# 14_Clocks_1.net
KiCad netlist of a schematic drawn in Altium Designer
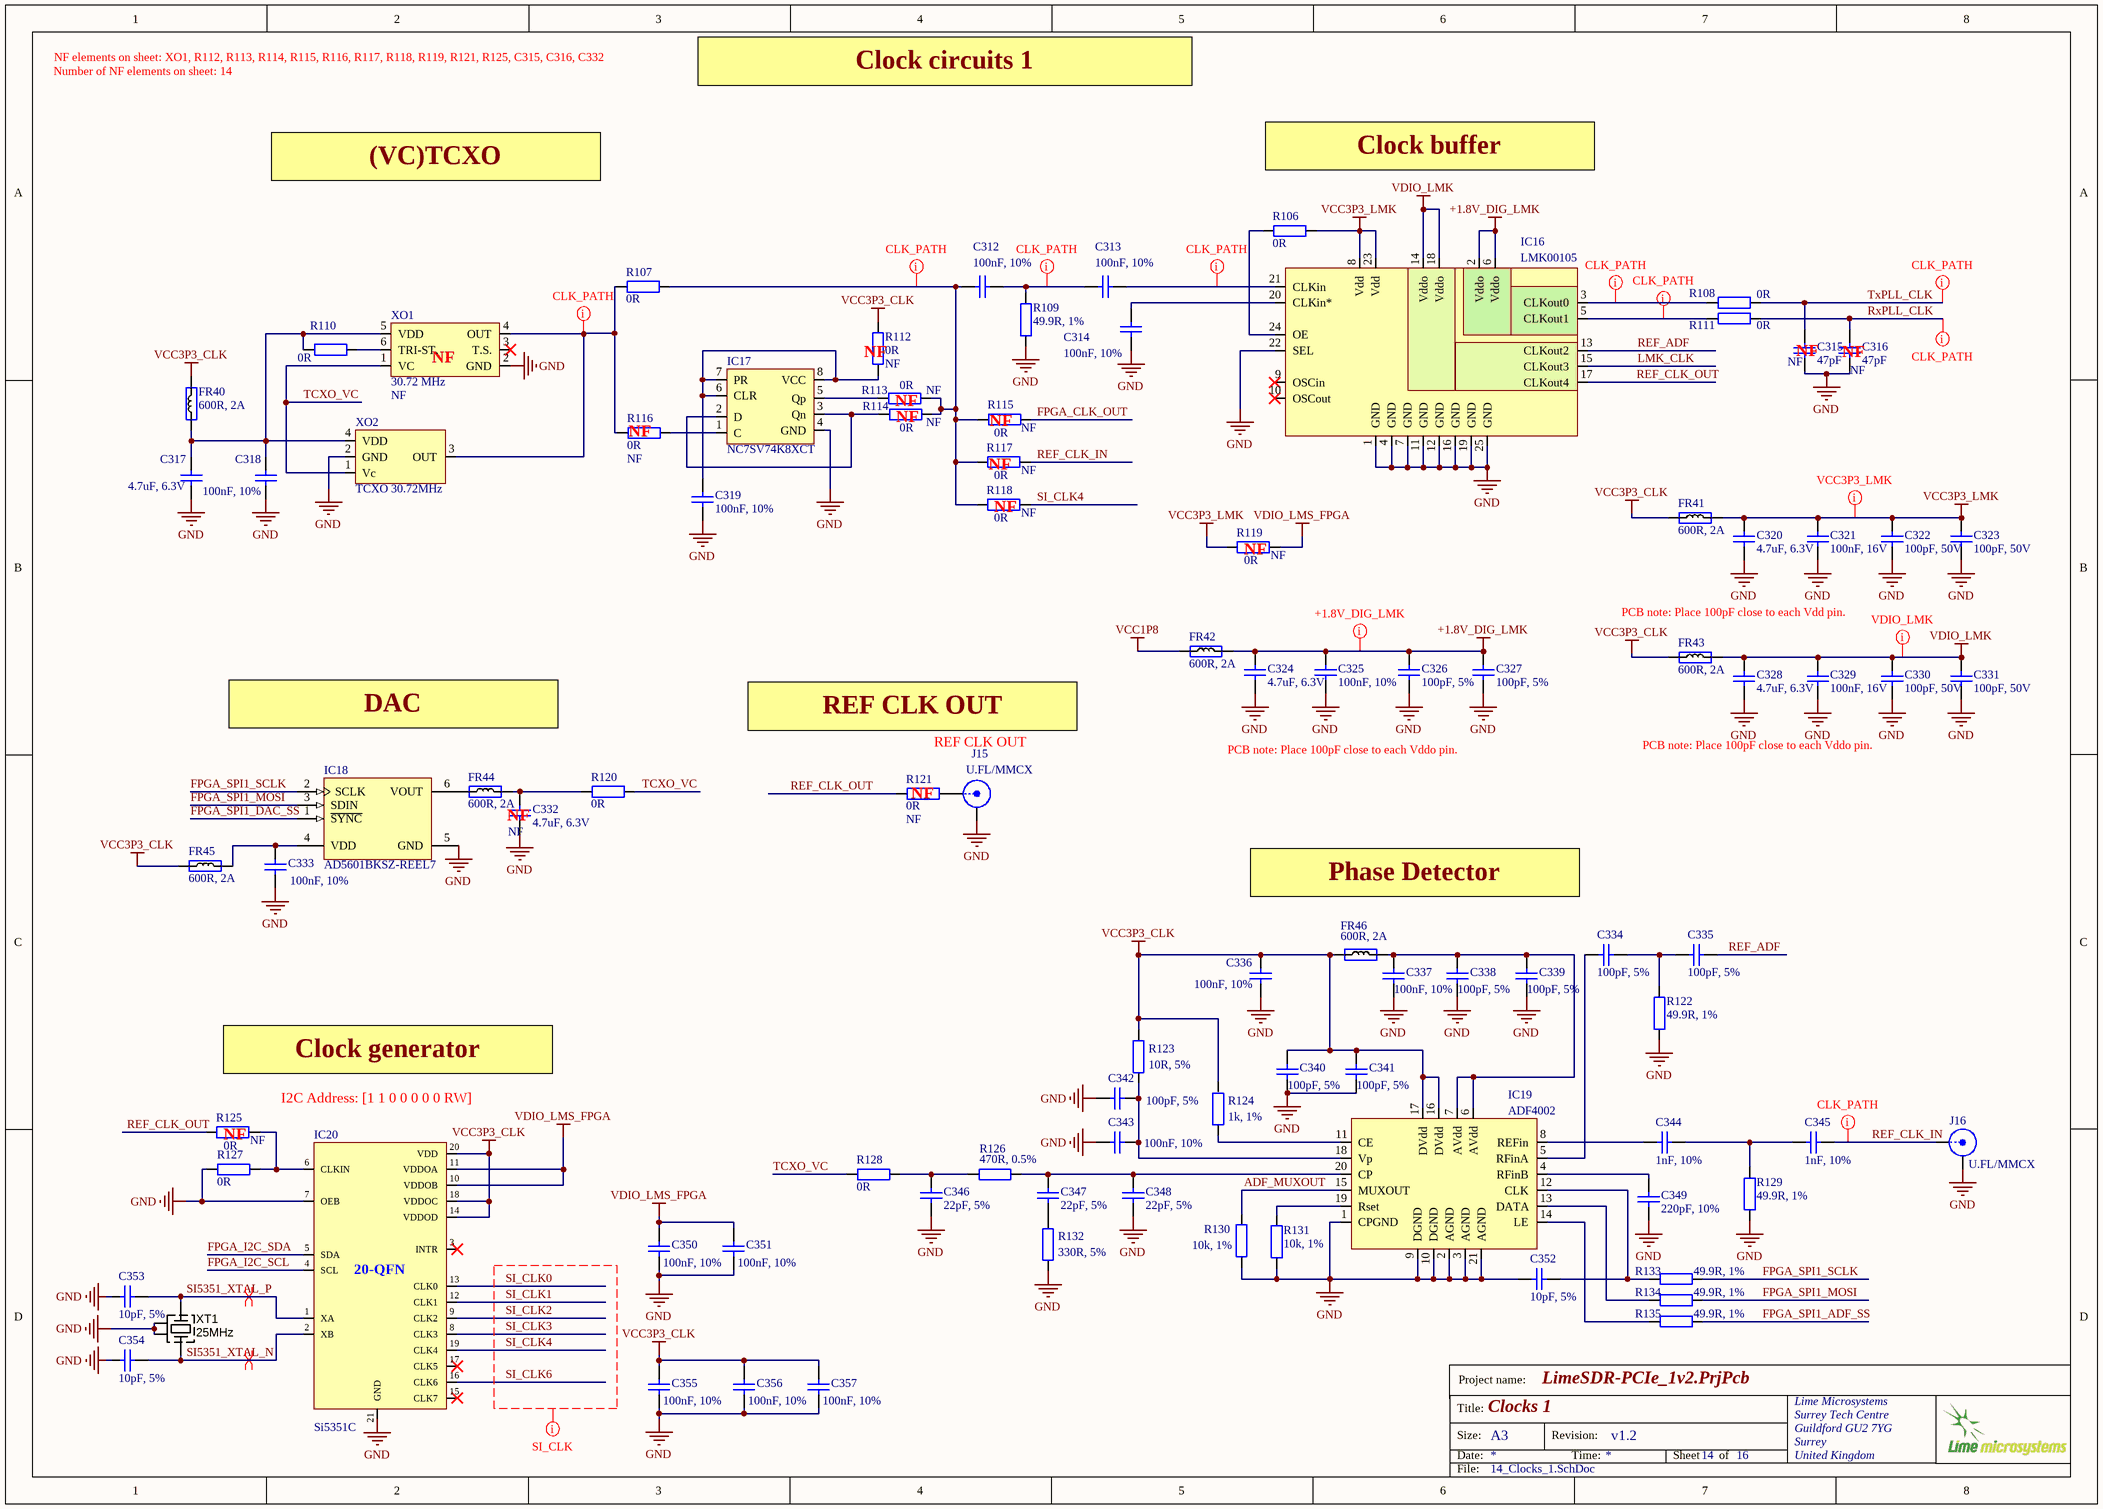
[diagram p0: 14_Clocks_1.SchDoc]

(export (version "E")
  (design (tool "Eeschema 10.0.6"))
  (components
    (comp (ref "C312")
      (value "100nF, 10%")
      (footprint "CAP0402")
      (fields
        (field (name "MANUFACTURER") "Murata Electronics")
        (field (name "TOLERANCE") "10 %")
        (field (name "MANUFACTURER PART NUMBER") "GRM155R71C104KA88D")
      )
      (libsource (lib "LimeMicroAltiumLib_schLib") (part "Cap_0402"))
    )
    (comp (ref "C313")
      (value "100nF, 10%")
      (footprint "CAP0402")
      (fields
        (field (name "MANUFACTURER") "Murata Electronics")
        (field (name "TOLERANCE") "10 %")
        (field (name "MANUFACTURER PART NUMBER") "GRM155R71C104KA88D")
      )
      (libsource (lib "LimeMicroAltiumLib_schLib") (part "Cap_0402"))
    )
    (comp (ref "C314")
      (value "100nF, 10%")
      (footprint "CAP0402")
      (fields
        (field (name "MANUFACTURER") "Murata Electronics")
        (field (name "TOLERANCE") "10 %")
        (field (name "MANUFACTURER PART NUMBER") "GRM155R71C104KA88D")
      )
      (libsource (lib "LimeMicroAltiumLib_schLib") (part "Cap_0402"))
    )
    (comp (ref "C315")
      (value "47pF")
      (footprint "CAP0402")
      (fields
        (field (name "TOLERANCE") "±1%")
        (field (name "MANUFACTURER") "TDK Corporation")
        (field (name "ASSEMBLY INFO") "NF")
      )
      (libsource (lib "LimeMicroAltiumLib_schLib") (part "Cap_0402"))
    )
    (comp (ref "C316")
      (value "47pF")
      (footprint "CAP0402")
      (fields
        (field (name "TOLERANCE") "±1%")
        (field (name "MANUFACTURER") "TDK Corporation")
        (field (name "ASSEMBLY INFO") "NF")
      )
      (libsource (lib "LimeMicroAltiumLib_schLib") (part "Cap_0402"))
    )
    (comp (ref "C317")
      (value "4.7uF, 6.3V")
      (footprint "CAP0402")
      (fields
        (field (name "MANUFACTURER") "Murata Electronics North America")
        (field (name "TOLERANCE") "±20%")
      )
      (libsource (lib "LimeMicroAltiumLib_schLib") (part "Cap_0402"))
    )
    (comp (ref "C318")
      (value "100nF, 10%")
      (footprint "CAP0402")
      (fields
        (field (name "MANUFACTURER") "Murata Electronics")
        (field (name "TOLERANCE") "10 %")
        (field (name "MANUFACTURER PART NUMBER") "GRM155R71C104KA88D")
      )
      (libsource (lib "LimeMicroAltiumLib_schLib") (part "Cap_0402"))
    )
    (comp (ref "C319")
      (value "100nF, 10%")
      (footprint "CAP0402")
      (fields
        (field (name "MANUFACTURER") "Murata Electronics")
        (field (name "TOLERANCE") "10 %")
        (field (name "MANUFACTURER PART NUMBER") "GRM155R71C104KA88D")
      )
      (libsource (lib "LimeMicroAltiumLib_schLib") (part "Cap_0402"))
    )
    (comp (ref "C320")
      (value "4.7uF, 6.3V")
      (footprint "CAP0402")
      (fields
        (field (name "MANUFACTURER") "Murata Electronics North America")
        (field (name "TOLERANCE") "±20%")
      )
      (libsource (lib "LimeMicroAltiumLib_schLib") (part "Cap_0402"))
    )
    (comp (ref "C321")
      (value "100nF, 16V")
      (footprint "CAP0402")
      (fields
        (field (name "MANUFACTURER") "Murata Electronics")
        (field (name "TOLERANCE") "10 %")
        (field (name "MANUFACTURER PART NUMBER") "GRM155R71C104KA88D")
      )
      (libsource (lib "LimeMicroAltiumLib_schLib") (part "Cap_0402"))
    )
    (comp (ref "C322")
      (value "100pF, 50V")
      (footprint "CAP0402")
      (fields (field (name "MANUFACTURER") "Yageo") (field (name "TOLERANCE") "±5%"))
      (libsource (lib "LimeMicroAltiumLib_schLib") (part "Cap_0402"))
    )
    (comp (ref "C323")
      (value "100pF, 50V")
      (footprint "CAP0402")
      (fields (field (name "MANUFACTURER") "Yageo") (field (name "TOLERANCE") "±5%"))
      (libsource (lib "LimeMicroAltiumLib_schLib") (part "Cap_0402"))
    )
    (comp (ref "C324")
      (value "4.7uF, 6.3V")
      (footprint "CAP0402")
      (fields
        (field (name "MANUFACTURER") "Murata Electronics North America")
        (field (name "TOLERANCE") "±20%")
      )
      (libsource (lib "LimeMicroAltiumLib_schLib") (part "Cap_0402"))
    )
    (comp (ref "C325")
      (value "100nF, 10%")
      (footprint "CAP0402")
      (fields
        (field (name "MANUFACTURER") "Murata Electronics")
        (field (name "TOLERANCE") "10 %")
        (field (name "MANUFACTURER PART NUMBER") "GRM155R71C104KA88D")
      )
      (libsource (lib "LimeMicroAltiumLib_schLib") (part "Cap_0402"))
    )
    (comp (ref "C326")
      (value "100pF, 5%")
      (footprint "CAP0402")
      (fields (field (name "MANUFACTURER") "Yageo") (field (name "TOLERANCE") "±5%"))
      (libsource (lib "LimeMicroAltiumLib_schLib") (part "Cap_0402"))
    )
    (comp (ref "C327")
      (value "100pF, 5%")
      (footprint "CAP0402")
      (fields (field (name "MANUFACTURER") "Yageo") (field (name "TOLERANCE") "±5%"))
      (libsource (lib "LimeMicroAltiumLib_schLib") (part "Cap_0402"))
    )
    (comp (ref "C328")
      (value "4.7uF, 6.3V")
      (footprint "CAP0402")
      (fields
        (field (name "MANUFACTURER") "Murata Electronics North America")
        (field (name "TOLERANCE") "±20%")
      )
      (libsource (lib "LimeMicroAltiumLib_schLib") (part "Cap_0402"))
    )
    (comp (ref "C329")
      (value "100nF, 16V")
      (footprint "CAP0402")
      (fields
        (field (name "MANUFACTURER") "Murata Electronics")
        (field (name "TOLERANCE") "10 %")
        (field (name "MANUFACTURER PART NUMBER") "GRM155R71C104KA88D")
      )
      (libsource (lib "LimeMicroAltiumLib_schLib") (part "Cap_0402"))
    )
    (comp (ref "C330")
      (value "100pF, 50V")
      (footprint "CAP0402")
      (fields (field (name "MANUFACTURER") "Yageo") (field (name "TOLERANCE") "±5%"))
      (libsource (lib "LimeMicroAltiumLib_schLib") (part "Cap_0402"))
    )
    (comp (ref "C331")
      (value "100pF, 50V")
      (footprint "CAP0402")
      (fields (field (name "MANUFACTURER") "Yageo") (field (name "TOLERANCE") "±5%"))
      (libsource (lib "LimeMicroAltiumLib_schLib") (part "Cap_0402"))
    )
    (comp (ref "C332")
      (value "4.7uF, 6.3V")
      (footprint "CAP0402")
      (fields
        (field (name "ASSEMBLY INFO") "NF")
        (field (name "MANUFACTURER") "Murata Electronics North America")
        (field (name "TOLERANCE") "±20%")
      )
      (libsource (lib "LimeMicroAltiumLib_schLib") (part "Cap_0402"))
    )
    (comp (ref "C333")
      (value "100nF, 10%")
      (footprint "CAP0402")
      (fields
        (field (name "TOLERANCE") "10 %")
        (field (name "MANUFACTURER") "Murata Electronics")
        (field (name "MANUFACTURER PART NUMBER") "GRM155R71C104KA88D")
      )
      (libsource (lib "LimeFPGAboard_schLib") (part "Cap_0603"))
    )
    (comp (ref "C334")
      (value "100pF, 5%")
      (footprint "CAP0402")
      (fields (field (name "MANUFACTURER") "Yageo") (field (name "TOLERANCE") "±5%"))
      (libsource (lib "LimeMicroAltiumLib_schLib") (part "Cap_0402"))
    )
    (comp (ref "C335")
      (value "100pF, 5%")
      (footprint "CAP0402")
      (fields (field (name "MANUFACTURER") "Yageo") (field (name "TOLERANCE") "±5%"))
      (libsource (lib "LimeMicroAltiumLib_schLib") (part "Cap_0402"))
    )
    (comp (ref "C336")
      (value "100nF, 10%")
      (footprint "CAP0402")
      (fields
        (field (name "MANUFACTURER") "Murata Electronics")
        (field (name "TOLERANCE") "10 %")
        (field (name "MANUFACTURER PART NUMBER") "GRM155R71C104KA88D")
      )
      (libsource (lib "LimeMicroAltiumLib_schLib") (part "Cap_0402"))
    )
    (comp (ref "C337")
      (value "100nF, 10%")
      (footprint "CAP0402")
      (fields
        (field (name "MANUFACTURER") "Murata Electronics")
        (field (name "TOLERANCE") "10 %")
        (field (name "MANUFACTURER PART NUMBER") "GRM155R71C104KA88D")
      )
      (libsource (lib "LimeMicroAltiumLib_schLib") (part "Cap_0402"))
    )
    (comp (ref "C338")
      (value "100pF, 5%")
      (footprint "CAP0402")
      (fields (field (name "MANUFACTURER") "Yageo") (field (name "TOLERANCE") "±5%"))
      (libsource (lib "LimeMicroAltiumLib_schLib") (part "Cap_0402"))
    )
    (comp (ref "C339")
      (value "100pF, 5%")
      (footprint "CAP0402")
      (fields (field (name "MANUFACTURER") "Yageo") (field (name "TOLERANCE") "±5%"))
      (libsource (lib "LimeMicroAltiumLib_schLib") (part "Cap_0402"))
    )
    (comp (ref "C340")
      (value "100pF, 5%")
      (footprint "CAP0402")
      (fields (field (name "MANUFACTURER") "Yageo") (field (name "TOLERANCE") "±5%"))
      (libsource (lib "LimeMicroAltiumLib_schLib") (part "Cap_0402"))
    )
    (comp (ref "C341")
      (value "100pF, 5%")
      (footprint "CAP0402")
      (fields (field (name "MANUFACTURER") "Yageo") (field (name "TOLERANCE") "±5%"))
      (libsource (lib "LimeMicroAltiumLib_schLib") (part "Cap_0402"))
    )
    (comp (ref "C342")
      (value "100pF, 5%")
      (footprint "CAP0402")
      (fields (field (name "MANUFACTURER") "Yageo") (field (name "TOLERANCE") "±5%"))
      (libsource (lib "LimeMicroAltiumLib_schLib") (part "Cap_0402"))
    )
    (comp (ref "C343")
      (value "100nF, 10%")
      (footprint "CAP0402")
      (fields
        (field (name "MANUFACTURER") "Murata Electronics")
        (field (name "TOLERANCE") "10 %")
        (field (name "MANUFACTURER PART NUMBER") "GRM155R71C104KA88D")
      )
      (libsource (lib "LimeMicroAltiumLib_schLib") (part "Cap_0402"))
    )
    (comp (ref "C344")
      (value "1nF, 10%")
      (footprint "CAP0402")
      (fields (field (name "TOLERANCE") "10 %") (field (name "MANUFACTURER") "Murata Electronics"))
      (libsource (lib "LimeMicroAltiumLib_schLib") (part "Cap_0402"))
    )
    (comp (ref "C345")
      (value "1nF, 10%")
      (footprint "CAP0402")
      (fields (field (name "TOLERANCE") "10 %") (field (name "MANUFACTURER") "Murata Electronics"))
      (libsource (lib "LimeMicroAltiumLib_schLib") (part "Cap_0402"))
    )
    (comp (ref "C346")
      (value "22pF, 5%")
      (footprint "CAP0402")
      (fields (field (name "TOLERANCE") "±5%") (field (name "MANUFACTURER") "Yageo"))
      (libsource (lib "LimeMicroAltiumLib_schLib") (part "Cap_0402"))
    )
    (comp (ref "C347")
      (value "22pF, 5%")
      (footprint "CAP0402")
      (fields (field (name "TOLERANCE") "±5%") (field (name "MANUFACTURER") "Yageo"))
      (libsource (lib "LimeMicroAltiumLib_schLib") (part "Cap_0402"))
    )
    (comp (ref "C348")
      (value "22pF, 5%")
      (footprint "CAP0402")
      (fields (field (name "TOLERANCE") "±5%") (field (name "MANUFACTURER") "Yageo"))
      (libsource (lib "LimeMicroAltiumLib_schLib") (part "Cap_0402"))
    )
    (comp (ref "C349")
      (value "220pF, 10%")
      (footprint "CAP0402")
      (fields (field (name "MANUFACTURER") "Yageo") (field (name "TOLERANCE") "±10%"))
      (libsource (lib "LimeMicroAltiumLib_schLib") (part "Cap_0402"))
    )
    (comp (ref "C350")
      (value "100nF, 10%")
      (footprint "CAP0402")
      (fields
        (field (name "TOLERANCE") "10 %")
        (field (name "MANUFACTURER") "Murata Electronics")
        (field (name "MANUFACTURER PART NUMBER") "GRM155R71C104KA88D")
      )
      (libsource (lib "LimeFPGAboard_schLib") (part "Cap_0603"))
    )
    (comp (ref "C351")
      (value "100nF, 10%")
      (footprint "CAP0402")
      (fields
        (field (name "TOLERANCE") "10 %")
        (field (name "MANUFACTURER") "Murata Electronics")
        (field (name "MANUFACTURER PART NUMBER") "GRM155R71C104KA88D")
      )
      (libsource (lib "LimeFPGAboard_schLib") (part "Cap_0603"))
    )
    (comp (ref "C352")
      (value "10pF, 5%")
      (footprint "CAP0402")
      (fields (field (name "MANUFACTURER") "AVX"))
      (libsource (lib "LimeMicroAltiumLib_schLib") (part "Cap_0402"))
    )
    (comp (ref "C353")
      (value "10pF, 5%")
      (footprint "CAP0402")
      (fields (field (name "MANUFACTURER") "AVX"))
      (libsource (lib "LimeFPGAboard_schLib") (part "Cap_0402"))
    )
    (comp (ref "C354")
      (value "10pF, 5%")
      (footprint "CAP0402")
      (fields (field (name "MANUFACTURER") "AVX"))
      (libsource (lib "LimeFPGAboard_schLib") (part "Cap_0402"))
    )
    (comp (ref "C355")
      (value "100nF, 10%")
      (footprint "CAP0402")
      (fields
        (field (name "TOLERANCE") "10 %")
        (field (name "MANUFACTURER") "Murata Electronics")
        (field (name "MANUFACTURER PART NUMBER") "GRM155R71C104KA88D")
      )
      (libsource (lib "LimeFPGAboard_schLib") (part "Cap_0603"))
    )
    (comp (ref "C356")
      (value "100nF, 10%")
      (footprint "CAP0402")
      (fields
        (field (name "TOLERANCE") "10 %")
        (field (name "MANUFACTURER") "Murata Electronics")
        (field (name "MANUFACTURER PART NUMBER") "GRM155R71C104KA88D")
      )
      (libsource (lib "LimeFPGAboard_schLib") (part "Cap_0603"))
    )
    (comp (ref "C357")
      (value "100nF, 10%")
      (footprint "CAP0402")
      (fields
        (field (name "TOLERANCE") "10 %")
        (field (name "MANUFACTURER") "Murata Electronics")
        (field (name "MANUFACTURER PART NUMBER") "GRM155R71C104KA88D")
      )
      (libsource (lib "LimeFPGAboard_schLib") (part "Cap_0603"))
    )
    (comp (ref "FR40")
      (value "600R, 2A")
      (footprint "RES0805")
      (fields (field (name "MANUFACTURER") "TDK Corporation"))
      (libsource (lib "LimeMicroAltiumLib_schLib") (part "Ferrite"))
    )
    (comp (ref "FR41")
      (value "600R, 2A")
      (footprint "RES0805")
      (fields (field (name "MANUFACTURER") "TDK Corporation"))
      (libsource (lib "LimeMicroAltiumLib_schLib") (part "Ferrite"))
    )
    (comp (ref "FR42")
      (value "600R, 2A")
      (footprint "RES0805")
      (fields (field (name "MANUFACTURER") "TDK Corporation"))
      (libsource (lib "LimeMicroAltiumLib_schLib") (part "Ferrite"))
    )
    (comp (ref "FR43")
      (value "600R, 2A")
      (footprint "RES0805")
      (fields (field (name "MANUFACTURER") "TDK Corporation"))
      (libsource (lib "LimeMicroAltiumLib_schLib") (part "Ferrite"))
    )
    (comp (ref "FR44")
      (value "600R, 2A")
      (footprint "RES0805")
      (fields (field (name "MANUFACTURER") "TDK Corporation"))
      (libsource (lib "LimeMicroAltiumLib_schLib") (part "Ferrite"))
    )
    (comp (ref "FR45")
      (value "600R, 2A")
      (footprint "RES0805")
      (fields (field (name "MANUFACTURER") "TDK Corporation"))
      (libsource (lib "LimeMicroAltiumLib_schLib") (part "Ferrite"))
    )
    (comp (ref "FR46")
      (value "600R, 2A")
      (footprint "RES0805")
      (fields (field (name "MANUFACTURER") "TDK Corporation"))
      (libsource (lib "LimeMicroAltiumLib_schLib") (part "Ferrite"))
    )
    (comp (ref "IC16")
      (value "LMK00105")
      (footprint "LMK00105SQ")
      (fields (field (name "MANUFACTURER") "Texas Instruments"))
      (libsource (lib "LimeMicroAltiumLib_schLib") (part "LMK00105"))
    )
    (comp (ref "IC17")
      (value "NC7SV74K8XCT")
      (footprint "NC7SV74K8XCT")
      (fields (field (name "MANUFACTURER") "Fairchild Semiconductor"))
      (libsource (lib "LimeMicroAltiumLib_schLib") (part "NC7SV74K8XCT"))
    )
    (comp (ref "IC18")
      (value "AD5601BKSZ-REEL7")
      (footprint "AD5601_SOT23-6")
      (fields (field (name "GENERIC PART NUMBER") "AD5601") (field (name "MANUFACTURER") "Analog Devices"))
      (libsource (lib "LimeMicroAltiumLib_schLib") (part "AD5601BKSZ-REEL7"))
    )
    (comp (ref "IC19")
      (value "ADF4002")
      (footprint "ADF4002")
      (fields (field (name "MANUFACTURER") "Analog Devices Inc"))
      (libsource (lib "LimeMicroAltiumLib_schLib") (part "ADF4002"))
    )
    (comp (ref "IC20")
      (value "Si5351C")
      (footprint "Si5351C_20QFN")
      (fields (field (name "MANUFACTURER") "Silicon Labs"))
      (libsource (lib "LimeFPGAboard_schLib") (part "Si5351C"))
    )
    (comp (ref "J15")
      (value "U.FL/MMCX")
      (footprint "MMCX_UFL_conn_u")
      (fields (field (name "MANUFACTURER") "Molex, LLC"))
      (libsource (lib "LimeMicroAltiumLib_schLib") (part "RF_IF_connector"))
    )
    (comp (ref "J16")
      (value "U.FL/MMCX")
      (footprint "MMCX_UFL_conn_u")
      (fields (field (name "MANUFACTURER") "Molex, LLC"))
      (libsource (lib "LimeMicroAltiumLib_schLib") (part "RF_IF_connector"))
    )
    (comp (ref "R106")
      (value "0R")
      (footprint "RES0402")
      (fields (field (name "MANUFACTURER") "Yageo") (field (name "TOLERANCE") "Jumper"))
      (libsource (lib "LimeMicroAltiumLib_schLib") (part "Res_0402"))
    )
    (comp (ref "R107")
      (value "0R")
      (footprint "RES0402")
      (fields (field (name "MANUFACTURER") "Yageo") (field (name "TOLERANCE") "Jumper"))
      (libsource (lib "LimeMicroAltiumLib_schLib") (part "Res_0402"))
    )
    (comp (ref "R108")
      (value "0R")
      (footprint "RES0402")
      (fields (field (name "MANUFACTURER") "Yageo") (field (name "TOLERANCE") "Jumper"))
      (libsource (lib "LimeMicroAltiumLib_schLib") (part "Res_0402"))
    )
    (comp (ref "R109")
      (value "49.9R, 1%")
      (footprint "RES0402")
      (fields
        (field (name "TOLERANCE") "±1%")
        (field (name "MANUFACTURER") "Samsung Electro-Mechanics America, Inc.")
        (field (name "MANUFACTURER PART NUMBER") "RC1005F49R9CS")
      )
      (libsource (lib "LimeMicroAltiumLib_schLib") (part "Res_0402"))
    )
    (comp (ref "R110")
      (value "0R")
      (footprint "RES0402")
      (fields (field (name "MANUFACTURER") "Yageo") (field (name "TOLERANCE") "Jumper"))
      (libsource (lib "LimeMicroAltiumLib_schLib") (part "Res_0402"))
    )
    (comp (ref "R111")
      (value "0R")
      (footprint "RES0402")
      (fields (field (name "MANUFACTURER") "Yageo") (field (name "TOLERANCE") "Jumper"))
      (libsource (lib "LimeMicroAltiumLib_schLib") (part "Res_0402"))
    )
    (comp (ref "R112")
      (value "0R")
      (footprint "RES0402")
      (fields
        (field (name "ASSEMBLY INFO") "NF")
        (field (name "MANUFACTURER") "Yageo")
        (field (name "TOLERANCE") "Jumper")
      )
      (libsource (lib "LimeMicroAltiumLib_schLib") (part "Res_0402"))
    )
    (comp (ref "R113")
      (value "0R")
      (footprint "RES0402")
      (fields
        (field (name "ASSEMBLY INFO") "NF")
        (field (name "MANUFACTURER") "Yageo")
        (field (name "TOLERANCE") "Jumper")
      )
      (libsource (lib "LimeMicroAltiumLib_schLib") (part "Res_0402"))
    )
    (comp (ref "R114")
      (value "0R")
      (footprint "RES0402")
      (fields
        (field (name "ASSEMBLY INFO") "NF")
        (field (name "MANUFACTURER") "Yageo")
        (field (name "TOLERANCE") "Jumper")
      )
      (libsource (lib "LimeMicroAltiumLib_schLib") (part "Res_0402"))
    )
    (comp (ref "R115")
      (value "0R")
      (footprint "RES0402")
      (fields
        (field (name "ASSEMBLY INFO") "NF")
        (field (name "MANUFACTURER") "Yageo")
        (field (name "TOLERANCE") "Jumper")
      )
      (libsource (lib "LimeMicroAltiumLib_schLib") (part "Res_0402"))
    )
    (comp (ref "R116")
      (value "0R")
      (footprint "RES0402")
      (fields
        (field (name "ASSEMBLY INFO") "NF")
        (field (name "MANUFACTURER") "Yageo")
        (field (name "TOLERANCE") "Jumper")
      )
      (libsource (lib "LimeMicroAltiumLib_schLib") (part "Res_0402"))
    )
    (comp (ref "R117")
      (value "0R")
      (footprint "RES0402")
      (fields
        (field (name "ASSEMBLY INFO") "NF")
        (field (name "MANUFACTURER") "Yageo")
        (field (name "TOLERANCE") "Jumper")
      )
      (libsource (lib "LimeMicroAltiumLib_schLib") (part "Res_0402"))
    )
    (comp (ref "R118")
      (value "0R")
      (footprint "RES0402")
      (fields
        (field (name "ASSEMBLY INFO") "NF")
        (field (name "MANUFACTURER") "Yageo")
        (field (name "TOLERANCE") "Jumper")
      )
      (libsource (lib "LimeMicroAltiumLib_schLib") (part "Res_0402"))
    )
    (comp (ref "R119")
      (value "0R")
      (footprint "RES0402")
      (fields
        (field (name "ASSEMBLY INFO") "NF")
        (field (name "MANUFACTURER") "Yageo")
        (field (name "TOLERANCE") "Jumper")
      )
      (libsource (lib "LimeMicroAltiumLib_schLib") (part "Res_0402"))
    )
    (comp (ref "R120")
      (value "0R")
      (footprint "RES0402")
      (fields (field (name "MANUFACTURER") "Yageo") (field (name "TOLERANCE") "Jumper"))
      (libsource (lib "LimeMicroAltiumLib_schLib") (part "Res_0402"))
    )
    (comp (ref "R121")
      (value "0R")
      (footprint "RES0402")
      (fields
        (field (name "ASSEMBLY INFO") "NF")
        (field (name "MANUFACTURER") "Yageo")
        (field (name "TOLERANCE") "Jumper")
      )
      (libsource (lib "LimeMicroAltiumLib_schLib") (part "Res_0402"))
    )
    (comp (ref "R122")
      (value "49.9R, 1%")
      (footprint "RES0402")
      (fields
        (field (name "TOLERANCE") "±1%")
        (field (name "MANUFACTURER") "Samsung Electro-Mechanics America, Inc.")
        (field (name "MANUFACTURER PART NUMBER") "RC1005F49R9CS")
      )
      (libsource (lib "LimeMicroAltiumLib_schLib") (part "Res_0402"))
    )
    (comp (ref "R123")
      (value "10R, 5%")
      (footprint "RES0402")
      (fields (field (name "TOLERANCE") "±5%") (field (name "MANUFACTURER") "Yageo"))
      (libsource (lib "LimeMicroAltiumLib_schLib") (part "Res_0402"))
    )
    (comp (ref "R124")
      (value "1k, 1%")
      (footprint "RES0402")
      (fields (field (name "MANUFACTURER") "Stackpole Electronics Inc") (field (name "TOLERANCE") "±1%"))
      (libsource (lib "LimeMicroAltiumLib_schLib") (part "Res_0402"))
    )
    (comp (ref "R125")
      (value "0R")
      (footprint "RES0402")
      (fields
        (field (name "ASSEMBLY INFO") "NF")
        (field (name "MANUFACTURER") "Yageo")
        (field (name "TOLERANCE") "Jumper")
      )
      (libsource (lib "LimeMicroAltiumLib_schLib") (part "Res_0402"))
    )
    (comp (ref "R126")
      (value "470R, 0.5%")
      (footprint "RES0402")
      (fields
        (field (name "TOLERANCE") "±0.5%")
        (field (name "MANUFACTURER") "Panasonic Electronic Components")
      )
      (libsource (lib "LimeMicroAltiumLib_schLib") (part "Res_0402"))
    )
    (comp (ref "R127")
      (value "0R")
      (footprint "RES0402")
      (fields (field (name "MANUFACTURER") "Yageo") (field (name "TOLERANCE") "Jumper"))
      (libsource (lib "LimeMicroAltiumLib_schLib") (part "Res_0402"))
    )
    (comp (ref "R128")
      (value "0R")
      (footprint "RES0402")
      (fields (field (name "MANUFACTURER") "Yageo") (field (name "TOLERANCE") "Jumper"))
      (libsource (lib "LimeMicroAltiumLib_schLib") (part "Res_0402"))
    )
    (comp (ref "R129")
      (value "49.9R, 1%")
      (footprint "RES0402")
      (fields
        (field (name "TOLERANCE") "±1%")
        (field (name "MANUFACTURER") "Samsung Electro-Mechanics America, Inc.")
        (field (name "MANUFACTURER PART NUMBER") "RC1005F49R9CS")
      )
      (libsource (lib "LimeMicroAltiumLib_schLib") (part "Res_0402"))
    )
    (comp (ref "R130")
      (value "10k, 1%")
      (footprint "RES0402")
      (fields (field (name "MANUFACTURER") "Yageo") (field (name "TOLERANCE") "±1%"))
      (libsource (lib "LimeMicroAltiumLib_schLib") (part "Res_0402"))
    )
    (comp (ref "R131")
      (value "10k, 1%")
      (footprint "RES0402")
      (fields (field (name "MANUFACTURER") "Yageo") (field (name "TOLERANCE") "±1%"))
      (libsource (lib "LimeMicroAltiumLib_schLib") (part "Res_0402"))
    )
    (comp (ref "R132")
      (value "330R, 5%")
      (footprint "RES0402")
      (fields (field (name "MANUFACTURER") "Yageo") (field (name "TOLERANCE") "±5%"))
      (libsource (lib "LimeMicroAltiumLib_schLib") (part "Res_0402"))
    )
    (comp (ref "R133")
      (value "49.9R, 1%")
      (footprint "RES0402")
      (fields
        (field (name "TOLERANCE") "±1%")
        (field (name "MANUFACTURER") "Samsung Electro-Mechanics America, Inc.")
        (field (name "MANUFACTURER PART NUMBER") "RC1005F49R9CS")
      )
      (libsource (lib "LimeMicroAltiumLib_schLib") (part "Res_0402"))
    )
    (comp (ref "R134")
      (value "49.9R, 1%")
      (footprint "RES0402")
      (fields
        (field (name "TOLERANCE") "±1%")
        (field (name "MANUFACTURER") "Samsung Electro-Mechanics America, Inc.")
        (field (name "MANUFACTURER PART NUMBER") "RC1005F49R9CS")
      )
      (libsource (lib "LimeMicroAltiumLib_schLib") (part "Res_0402"))
    )
    (comp (ref "R135")
      (value "49.9R, 1%")
      (footprint "RES0402")
      (fields
        (field (name "TOLERANCE") "±1%")
        (field (name "MANUFACTURER") "Samsung Electro-Mechanics America, Inc.")
        (field (name "MANUFACTURER PART NUMBER") "RC1005F49R9CS")
      )
      (libsource (lib "LimeMicroAltiumLib_schLib") (part "Res_0402"))
    )
    (comp (ref "XO1")
      (value "30.72 MHz")
      (footprint "RAKON_RPT7050A")
      (fields (field (name "ASSEMBLY INFO") "NF") (field (name "MANUFACTURER") "Rakon"))
      (libsource (lib "LimeMicroAltiumLib_schLib") (part "RPT7050A"))
    )
    (comp (ref "XO2")
      (value "TCXO 30.72MHz")
      (footprint "RAKON_TXCO")
      (fields (field (name "MANUFACTURER") "Rakon"))
      (libsource (lib "LimeMicroAltiumLib_schLib") (part "TXCO"))
    )
    (comp (ref "XT1")
      (value "25MHz")
      (footprint "CRYSTAL_4-LCC")
      (description "Oscillator Crystal 25 MHz")
      (fields (field (name "MANUFACTURER") "ABRACON"))
      (libsource (lib "LimeFPGAboard_schLib") (part "CRYSTAL_19M2"))
    )
  )
  (nets
    (net (code "1") (name "+1.8V_DIG_LMK") (class "Default")
      (node (ref "C324") (pin "2") (pinfunction "2_2") (pintype "passive"))
      (node (ref "C325") (pin "2") (pinfunction "2_2") (pintype "passive"))
      (node (ref "C326") (pin "2") (pinfunction "2_2") (pintype "passive"))
      (node (ref "C327") (pin "2") (pinfunction "2_2") (pintype "passive"))
      (node (ref "FR42") (pin "2") (pinfunction "2_2") (pintype "passive"))
      (node (ref "IC16") (pin "2") (pinfunction "Vddo_2") (pintype "passive"))
      (node (ref "IC16") (pin "6") (pinfunction "Vddo_6") (pintype "passive"))
    )
    (net (code "2") (name "/ADF_MUXOUT") (class "Default")
      (node (ref "IC19") (pin "15") (pinfunction "MUXOUT_15") (pintype "passive"))
      (node (ref "R130") (pin "1") (pinfunction "1_1") (pintype "passive"))
    )
    (net (code "3") (name "/FPGA_CLK_OUT") (class "Default")
      (node (ref "R115") (pin "1") (pinfunction "1_1") (pintype "passive"))
    )
    (net (code "4") (name "/FPGA_I2C_SCL") (class "Default")
      (node (ref "IC20") (pin "4") (pinfunction "SCL_4") (pintype "passive"))
    )
    (net (code "5") (name "/FPGA_I2C_SDA") (class "Default")
      (node (ref "IC20") (pin "5") (pinfunction "SDA_5") (pintype "passive"))
    )
    (net (code "6") (name "/FPGA_SPI1_ADF_SS") (class "Default")
      (node (ref "R135") (pin "1") (pinfunction "1_1") (pintype "passive"))
    )
    (net (code "7") (name "/FPGA_SPI1_DAC_SS") (class "Default")
      (node (ref "IC18") (pin "1") (pinfunction "~{SYNC}_1") (pintype "input"))
    )
    (net (code "8") (name "/FPGA_SPI1_MOSI") (class "Default")
      (node (ref "IC18") (pin "3") (pinfunction "SDIN_3") (pintype "input"))
      (node (ref "R134") (pin "1") (pinfunction "1_1") (pintype "passive"))
    )
    (net (code "9") (name "/FPGA_SPI1_SCLK") (class "Default")
      (node (ref "IC18") (pin "2") (pinfunction "SCLK_2") (pintype "input"))
      (node (ref "R133") (pin "1") (pinfunction "1_1") (pintype "passive"))
    )
    (net (code "10") (name "/LMK_CLK") (class "Default")
      (node (ref "IC16") (pin "15") (pinfunction "CLKout3_15") (pintype "passive"))
    )
    (net (code "11") (name "/REF_ADF") (class "Default")
      (node (ref "C335") (pin "2") (pinfunction "2_2") (pintype "passive"))
      (node (ref "IC16") (pin "13") (pinfunction "CLKout2_13") (pintype "passive"))
    )
    (net (code "12") (name "/REF_CLK_IN") (class "Default")
      (node (ref "C345") (pin "1") (pinfunction "1_1") (pintype "passive"))
      (node (ref "J16") (pin "1") (pinfunction "X_1") (pintype "passive"))
      (node (ref "R117") (pin "2") (pinfunction "2_2") (pintype "passive"))
    )
    (net (code "13") (name "/REF_CLK_OUT") (class "Default")
      (node (ref "IC16") (pin "17") (pinfunction "CLKout4_17") (pintype "passive"))
      (node (ref "R121") (pin "2") (pinfunction "2_2") (pintype "passive"))
      (node (ref "R125") (pin "1") (pinfunction "1_1") (pintype "passive"))
    )
    (net (code "14") (name "/RxPLL_CLK") (class "Default")
      (node (ref "C316") (pin "2") (pinfunction "2_2") (pintype "passive"))
      (node (ref "R111") (pin "1") (pinfunction "1_1") (pintype "passive"))
    )
    (net (code "15") (name "/SI5351_XTAL_N") (class "Default")
      (node (ref "C354") (pin "2") (pinfunction "2_2") (pintype "passive"))
      (node (ref "IC20") (pin "2") (pinfunction "XB_2") (pintype "passive"))
      (node (ref "XT1") (pin "3") (pinfunction "X_3") (pintype "passive"))
    )
    (net (code "16") (name "/SI5351_XTAL_P") (class "Default")
      (node (ref "C353") (pin "2") (pinfunction "2_2") (pintype "passive"))
      (node (ref "IC20") (pin "1") (pinfunction "XA_1") (pintype "passive"))
      (node (ref "XT1") (pin "1") (pinfunction "X_1") (pintype "passive"))
    )
    (net (code "17") (name "/SI_CLK0") (class "Default")
      (node (ref "IC20") (pin "13") (pinfunction "CLK0_13") (pintype "passive"))
    )
    (net (code "18") (name "/SI_CLK1") (class "Default")
      (node (ref "IC20") (pin "12") (pinfunction "CLK1_12") (pintype "passive"))
    )
    (net (code "19") (name "/SI_CLK2") (class "Default")
      (node (ref "IC20") (pin "9") (pinfunction "CLK2_9") (pintype "passive"))
    )
    (net (code "20") (name "/SI_CLK3") (class "Default")
      (node (ref "IC20") (pin "8") (pinfunction "CLK3_8") (pintype "passive"))
    )
    (net (code "21") (name "/SI_CLK4") (class "Default")
      (node (ref "IC20") (pin "19") (pinfunction "CLK4_19") (pintype "passive"))
      (node (ref "R118") (pin "2") (pinfunction "2_2") (pintype "passive"))
    )
    (net (code "22") (name "/SI_CLK6") (class "Default")
      (node (ref "IC20") (pin "16") (pinfunction "CLK6_16") (pintype "passive"))
    )
    (net (code "23") (name "/TCXO_VC") (class "Default")
      (node (ref "R120") (pin "1") (pinfunction "1_1") (pintype "passive"))
      (node (ref "R128") (pin "2") (pinfunction "2_2") (pintype "passive"))
      (node (ref "XO1") (pin "1") (pinfunction "VC_1") (pintype "passive"))
      (node (ref "XO2") (pin "1") (pinfunction "Vc_1") (pintype "passive"))
    )
    (net (code "24") (name "/TxPLL_CLK") (class "Default")
      (node (ref "C315") (pin "2") (pinfunction "2_2") (pintype "passive"))
      (node (ref "R108") (pin "1") (pinfunction "1_1") (pintype "passive"))
    )
    (net (code "25") (name "GND") (class "Default")
      (node (ref "C314") (pin "1") (pinfunction "1_1") (pintype "passive"))
      (node (ref "C315") (pin "1") (pinfunction "1_1") (pintype "passive"))
      (node (ref "C316") (pin "1") (pinfunction "1_1") (pintype "passive"))
      (node (ref "C317") (pin "1") (pinfunction "1_1") (pintype "passive"))
      (node (ref "C318") (pin "1") (pinfunction "1_1") (pintype "passive"))
      (node (ref "C319") (pin "1") (pinfunction "1_1") (pintype "passive"))
      (node (ref "C320") (pin "1") (pinfunction "1_1") (pintype "passive"))
      (node (ref "C321") (pin "1") (pinfunction "1_1") (pintype "passive"))
      (node (ref "C322") (pin "1") (pinfunction "1_1") (pintype "passive"))
      (node (ref "C323") (pin "1") (pinfunction "1_1") (pintype "passive"))
      (node (ref "C324") (pin "1") (pinfunction "1_1") (pintype "passive"))
      (node (ref "C325") (pin "1") (pinfunction "1_1") (pintype "passive"))
      (node (ref "C326") (pin "1") (pinfunction "1_1") (pintype "passive"))
      (node (ref "C327") (pin "1") (pinfunction "1_1") (pintype "passive"))
      (node (ref "C328") (pin "1") (pinfunction "1_1") (pintype "passive"))
      (node (ref "C329") (pin "1") (pinfunction "1_1") (pintype "passive"))
      (node (ref "C330") (pin "1") (pinfunction "1_1") (pintype "passive"))
      (node (ref "C331") (pin "1") (pinfunction "1_1") (pintype "passive"))
      (node (ref "C332") (pin "1") (pinfunction "1_1") (pintype "passive"))
      (node (ref "C333") (pin "2") (pinfunction "2_2") (pintype "passive"))
      (node (ref "C336") (pin "1") (pinfunction "1_1") (pintype "passive"))
      (node (ref "C337") (pin "1") (pinfunction "1_1") (pintype "passive"))
      (node (ref "C338") (pin "2") (pinfunction "2_2") (pintype "passive"))
      (node (ref "C339") (pin "2") (pinfunction "2_2") (pintype "passive"))
      (node (ref "C340") (pin "2") (pinfunction "2_2") (pintype "passive"))
      (node (ref "C341") (pin "2") (pinfunction "2_2") (pintype "passive"))
      (node (ref "C342") (pin "1") (pinfunction "1_1") (pintype "passive"))
      (node (ref "C343") (pin "2") (pinfunction "2_2") (pintype "passive"))
      (node (ref "C346") (pin "1") (pinfunction "1_1") (pintype "passive"))
      (node (ref "C348") (pin "1") (pinfunction "1_1") (pintype "passive"))
      (node (ref "C349") (pin "2") (pinfunction "2_2") (pintype "passive"))
      (node (ref "C350") (pin "2") (pinfunction "2_2") (pintype "passive"))
      (node (ref "C351") (pin "2") (pinfunction "2_2") (pintype "passive"))
      (node (ref "C352") (pin "1") (pinfunction "1_1") (pintype "passive"))
      (node (ref "C353") (pin "1") (pinfunction "1_1") (pintype "passive"))
      (node (ref "C354") (pin "1") (pinfunction "1_1") (pintype "passive"))
      (node (ref "C355") (pin "2") (pinfunction "2_2") (pintype "passive"))
      (node (ref "C356") (pin "2") (pinfunction "2_2") (pintype "passive"))
      (node (ref "C357") (pin "2") (pinfunction "2_2") (pintype "passive"))
      (node (ref "IC16") (pin "1") (pinfunction "GND_1") (pintype "passive"))
      (node (ref "IC16") (pin "11") (pinfunction "GND_11") (pintype "passive"))
      (node (ref "IC16") (pin "12") (pinfunction "GND_12") (pintype "passive"))
      (node (ref "IC16") (pin "16") (pinfunction "GND_16") (pintype "passive"))
      (node (ref "IC16") (pin "19") (pinfunction "GND_19") (pintype "passive"))
      (node (ref "IC16") (pin "22") (pinfunction "SEL_22") (pintype "passive"))
      (node (ref "IC16") (pin "25") (pinfunction "GND_25") (pintype "passive"))
      (node (ref "IC16") (pin "4") (pinfunction "GND_4") (pintype "passive"))
      (node (ref "IC16") (pin "7") (pinfunction "GND_7") (pintype "passive"))
      (node (ref "IC17") (pin "4") (pinfunction "GND_4") (pintype "passive"))
      (node (ref "IC18") (pin "5") (pinfunction "GND_5") (pintype "power_in"))
      (node (ref "IC19") (pin "1") (pinfunction "CPGND_1") (pintype "passive"))
      (node (ref "IC19") (pin "10") (pinfunction "DGND_10") (pintype "passive"))
      (node (ref "IC19") (pin "2") (pinfunction "AGND_2") (pintype "passive"))
      (node (ref "IC19") (pin "21") (pinfunction "AGND_21") (pintype "passive"))
      (node (ref "IC19") (pin "3") (pinfunction "AGND_3") (pintype "passive"))
      (node (ref "IC19") (pin "9") (pinfunction "DGND_9") (pintype "passive"))
      (node (ref "IC20") (pin "21") (pinfunction "GND_21") (pintype "passive"))
      (node (ref "IC20") (pin "7") (pinfunction "OEB_7") (pintype "passive"))
      (node (ref "J15") (pin "2") (pinfunction "Y_2") (pintype "passive"))
      (node (ref "J16") (pin "2") (pinfunction "Y_2") (pintype "passive"))
      (node (ref "R109") (pin "1") (pinfunction "1_1") (pintype "passive"))
      (node (ref "R122") (pin "1") (pinfunction "1_1") (pintype "passive"))
      (node (ref "R127") (pin "2") (pinfunction "2_2") (pintype "passive"))
      (node (ref "R129") (pin "1") (pinfunction "1_1") (pintype "passive"))
      (node (ref "R130") (pin "2") (pinfunction "2_2") (pintype "passive"))
      (node (ref "R131") (pin "2") (pinfunction "2_2") (pintype "passive"))
      (node (ref "R132") (pin "1") (pinfunction "1_1") (pintype "passive"))
      (node (ref "XO1") (pin "2") (pinfunction "GND_2") (pintype "passive"))
      (node (ref "XO2") (pin "2") (pinfunction "GND_2") (pintype "passive"))
      (node (ref "XT1") (pin "2") (pinfunction "GND_2") (pintype "passive"))
      (node (ref "XT1") (pin "4") (pinfunction "GND_4") (pintype "passive"))
    )
    (net (code "26") (name "Net-(C312-Pad1)") (class "Default")
      (node (ref "C312") (pin "1") (pinfunction "1_1") (pintype "passive"))
      (node (ref "C313") (pin "2") (pinfunction "2_2") (pintype "passive"))
      (node (ref "R109") (pin "2") (pinfunction "2_2") (pintype "passive"))
    )
    (net (code "27") (name "Net-(C312-Pad2)") (class "Default")
      (node (ref "C312") (pin "2") (pinfunction "2_2") (pintype "passive"))
      (node (ref "R107") (pin "1") (pinfunction "1_1") (pintype "passive"))
      (node (ref "R113") (pin "1") (pinfunction "1_1") (pintype "passive"))
      (node (ref "R114") (pin "1") (pinfunction "1_1") (pintype "passive"))
      (node (ref "R115") (pin "2") (pinfunction "2_2") (pintype "passive"))
      (node (ref "R117") (pin "1") (pinfunction "1_1") (pintype "passive"))
      (node (ref "R118") (pin "1") (pinfunction "1_1") (pintype "passive"))
    )
    (net (code "28") (name "Net-(C332-Pad2)") (class "Default")
      (node (ref "C332") (pin "2") (pinfunction "2_2") (pintype "passive"))
      (node (ref "FR44") (pin "2") (pinfunction "2_2") (pintype "passive"))
      (node (ref "R120") (pin "2") (pinfunction "2_2") (pintype "passive"))
    )
    (net (code "29") (name "Net-(C334-Pad2)") (class "Default")
      (node (ref "C334") (pin "2") (pinfunction "2_2") (pintype "passive"))
      (node (ref "C335") (pin "1") (pinfunction "1_1") (pintype "passive"))
      (node (ref "R122") (pin "2") (pinfunction "2_2") (pintype "passive"))
    )
    (net (code "30") (name "Net-(C337-Pad2)") (class "Default")
      (node (ref "C337") (pin "2") (pinfunction "2_2") (pintype "passive"))
      (node (ref "C338") (pin "1") (pinfunction "1_1") (pintype "passive"))
      (node (ref "C339") (pin "1") (pinfunction "1_1") (pintype "passive"))
      (node (ref "FR46") (pin "2") (pinfunction "2_2") (pintype "passive"))
      (node (ref "IC19") (pin "6") (pinfunction "AVdd_6") (pintype "passive"))
      (node (ref "IC19") (pin "7") (pinfunction "AVdd_7") (pintype "passive"))
    )
    (net (code "31") (name "Net-(C344-Pad1)") (class "Default")
      (node (ref "C344") (pin "1") (pinfunction "1_1") (pintype "passive"))
      (node (ref "C345") (pin "2") (pinfunction "2_2") (pintype "passive"))
      (node (ref "R129") (pin "2") (pinfunction "2_2") (pintype "passive"))
    )
    (net (code "32") (name "Net-(C346-Pad2)") (class "Default")
      (node (ref "C346") (pin "2") (pinfunction "2_2") (pintype "passive"))
      (node (ref "R126") (pin "2") (pinfunction "2_2") (pintype "passive"))
      (node (ref "R128") (pin "1") (pinfunction "1_1") (pintype "passive"))
    )
    (net (code "33") (name "Net-(C347-Pad1)") (class "Default")
      (node (ref "C347") (pin "1") (pinfunction "1_1") (pintype "passive"))
      (node (ref "R132") (pin "2") (pinfunction "2_2") (pintype "passive"))
    )
    (net (code "34") (name "Net-(IC16-CLKin)") (class "Default")
      (node (ref "C313") (pin "1") (pinfunction "1_1") (pintype "passive"))
      (node (ref "IC16") (pin "21") (pinfunction "CLKin_21") (pintype "passive"))
    )
    (net (code "35") (name "Net-(IC16-CLKin*)") (class "Default")
      (node (ref "C314") (pin "2") (pinfunction "2_2") (pintype "passive"))
      (node (ref "IC16") (pin "20") (pinfunction "CLKin*_20") (pintype "passive"))
    )
    (net (code "36") (name "Net-(IC16-CLKout0)") (class "Default")
      (node (ref "IC16") (pin "3") (pinfunction "CLKout0_3") (pintype "passive"))
      (node (ref "R108") (pin "2") (pinfunction "2_2") (pintype "passive"))
    )
    (net (code "37") (name "Net-(IC16-CLKout1)") (class "Default")
      (node (ref "IC16") (pin "5") (pinfunction "CLKout1_5") (pintype "passive"))
      (node (ref "R111") (pin "2") (pinfunction "2_2") (pintype "passive"))
    )
    (net (code "38") (name "Net-(IC16-OE)") (class "Default")
      (node (ref "IC16") (pin "24") (pinfunction "OE_24") (pintype "passive"))
      (node (ref "R106") (pin "1") (pinfunction "1_1") (pintype "passive"))
    )
    (net (code "39") (name "Net-(IC17-C)") (class "Default")
      (node (ref "IC17") (pin "1") (pinfunction "C_1") (pintype "passive"))
      (node (ref "R116") (pin "1") (pinfunction "1_1") (pintype "passive"))
    )
    (net (code "40") (name "Net-(IC17-CLR)") (class "Default")
      (node (ref "C319") (pin "2") (pinfunction "2_2") (pintype "passive"))
      (node (ref "IC17") (pin "6") (pinfunction "CLR_6") (pintype "passive"))
      (node (ref "IC17") (pin "7") (pinfunction "PR_7") (pintype "passive"))
      (node (ref "IC17") (pin "8") (pinfunction "VCC_8") (pintype "passive"))
      (node (ref "R112") (pin "2") (pinfunction "2_2") (pintype "passive"))
    )
    (net (code "41") (name "Net-(IC17-D)") (class "Default")
      (node (ref "IC17") (pin "2") (pinfunction "D_2") (pintype "passive"))
      (node (ref "IC17") (pin "3") (pinfunction "Qn_3") (pintype "passive"))
      (node (ref "R114") (pin "2") (pinfunction "2_2") (pintype "passive"))
    )
    (net (code "42") (name "Net-(IC17-Qp)") (class "Default")
      (node (ref "IC17") (pin "5") (pinfunction "Qp_5") (pintype "passive"))
      (node (ref "R113") (pin "2") (pinfunction "2_2") (pintype "passive"))
    )
    (net (code "43") (name "Net-(IC18-VDD)") (class "Default")
      (node (ref "C333") (pin "1") (pinfunction "1_1") (pintype "passive"))
      (node (ref "FR45") (pin "2") (pinfunction "2_2") (pintype "passive"))
      (node (ref "IC18") (pin "4") (pinfunction "VDD_4") (pintype "power_in"))
    )
    (net (code "44") (name "Net-(IC18-VOUT)") (class "Default")
      (node (ref "FR44") (pin "1") (pinfunction "1_1") (pintype "passive"))
      (node (ref "IC18") (pin "6") (pinfunction "VOUT_6") (pintype "tri_state"))
    )
    (net (code "45") (name "Net-(IC19-CE)") (class "Default")
      (node (ref "IC19") (pin "11") (pinfunction "CE_11") (pintype "passive"))
      (node (ref "R124") (pin "1") (pinfunction "1_1") (pintype "passive"))
    )
    (net (code "46") (name "Net-(IC19-CLK)") (class "Default")
      (node (ref "C352") (pin "2") (pinfunction "2_2") (pintype "passive"))
      (node (ref "IC19") (pin "12") (pinfunction "CLK_12") (pintype "passive"))
      (node (ref "R133") (pin "2") (pinfunction "2_2") (pintype "passive"))
    )
    (net (code "47") (name "Net-(IC19-CP)") (class "Default")
      (node (ref "C347") (pin "2") (pinfunction "2_2") (pintype "passive"))
      (node (ref "C348") (pin "2") (pinfunction "2_2") (pintype "passive"))
      (node (ref "IC19") (pin "20") (pinfunction "CP_20") (pintype "passive"))
      (node (ref "R126") (pin "1") (pinfunction "1_1") (pintype "passive"))
    )
    (net (code "48") (name "Net-(IC19-DATA)") (class "Default")
      (node (ref "IC19") (pin "13") (pinfunction "DATA_13") (pintype "passive"))
      (node (ref "R134") (pin "2") (pinfunction "2_2") (pintype "passive"))
    )
    (net (code "49") (name "Net-(IC19-LE)") (class "Default")
      (node (ref "IC19") (pin "14") (pinfunction "LE_14") (pintype "passive"))
      (node (ref "R135") (pin "2") (pinfunction "2_2") (pintype "passive"))
    )
    (net (code "50") (name "Net-(IC19-REFin)") (class "Default")
      (node (ref "C344") (pin "2") (pinfunction "2_2") (pintype "passive"))
      (node (ref "IC19") (pin "8") (pinfunction "REFin_8") (pintype "passive"))
    )
    (net (code "51") (name "Net-(IC19-RFinA)") (class "Default")
      (node (ref "C334") (pin "1") (pinfunction "1_1") (pintype "passive"))
      (node (ref "IC19") (pin "5") (pinfunction "RFinA_5") (pintype "passive"))
    )
    (net (code "52") (name "Net-(IC19-RFinB)") (class "Default")
      (node (ref "C349") (pin "1") (pinfunction "1_1") (pintype "passive"))
      (node (ref "IC19") (pin "4") (pinfunction "RFinB_4") (pintype "passive"))
    )
    (net (code "53") (name "Net-(IC19-Rset)") (class "Default")
      (node (ref "IC19") (pin "19") (pinfunction "Rset_19") (pintype "passive"))
      (node (ref "R131") (pin "1") (pinfunction "1_1") (pintype "passive"))
    )
    (net (code "54") (name "Net-(IC19-Vp)") (class "Default")
      (node (ref "C342") (pin "2") (pinfunction "2_2") (pintype "passive"))
      (node (ref "C343") (pin "1") (pinfunction "1_1") (pintype "passive"))
      (node (ref "IC19") (pin "18") (pinfunction "Vp_18") (pintype "passive"))
      (node (ref "R123") (pin "1") (pinfunction "1_1") (pintype "passive"))
    )
    (net (code "55") (name "Net-(IC20-CLKIN)") (class "Default")
      (node (ref "IC20") (pin "6") (pinfunction "CLKIN_6") (pintype "passive"))
      (node (ref "R125") (pin "2") (pinfunction "2_2") (pintype "passive"))
      (node (ref "R127") (pin "1") (pinfunction "1_1") (pintype "passive"))
    )
    (net (code "56") (name "Net-(J15-X)") (class "Default")
      (node (ref "J15") (pin "1") (pinfunction "X_1") (pintype "passive"))
      (node (ref "R121") (pin "1") (pinfunction "1_1") (pintype "passive"))
    )
    (net (code "57") (name "Net-(XO1-OUT)") (class "Default")
      (node (ref "R107") (pin "2") (pinfunction "2_2") (pintype "passive"))
      (node (ref "R116") (pin "2") (pinfunction "2_2") (pintype "passive"))
      (node (ref "XO1") (pin "4") (pinfunction "OUT_4") (pintype "passive"))
      (node (ref "XO2") (pin "3") (pinfunction "OUT_3") (pintype "passive"))
    )
    (net (code "58") (name "Net-(XO1-TRI-ST.)") (class "Default")
      (node (ref "R110") (pin "1") (pinfunction "1_1") (pintype "passive"))
      (node (ref "XO1") (pin "6") (pinfunction "TRI-ST._6") (pintype "passive"))
    )
    (net (code "59") (name "Net-(XO1-VDD)") (class "Default")
      (node (ref "C317") (pin "2") (pinfunction "2_2") (pintype "passive"))
      (node (ref "C318") (pin "2") (pinfunction "2_2") (pintype "passive"))
      (node (ref "FR40") (pin "1") (pinfunction "1_1") (pintype "passive"))
      (node (ref "R110") (pin "2") (pinfunction "2_2") (pintype "passive"))
      (node (ref "XO1") (pin "5") (pinfunction "VDD_5") (pintype "passive"))
      (node (ref "XO2") (pin "4") (pinfunction "VDD_4") (pintype "passive"))
    )
    (net (code "60") (name "VCC1P8") (class "Default")
      (node (ref "FR42") (pin "1") (pinfunction "1_1") (pintype "passive"))
    )
    (net (code "61") (name "VCC3P3_CLK") (class "Default")
      (node (ref "C336") (pin "2") (pinfunction "2_2") (pintype "passive"))
      (node (ref "C340") (pin "1") (pinfunction "1_1") (pintype "passive"))
      (node (ref "C341") (pin "1") (pinfunction "1_1") (pintype "passive"))
      (node (ref "C355") (pin "1") (pinfunction "1_1") (pintype "passive"))
      (node (ref "C356") (pin "1") (pinfunction "1_1") (pintype "passive"))
      (node (ref "C357") (pin "1") (pinfunction "1_1") (pintype "passive"))
      (node (ref "FR40") (pin "2") (pinfunction "2_2") (pintype "passive"))
      (node (ref "FR41") (pin "1") (pinfunction "1_1") (pintype "passive"))
      (node (ref "FR43") (pin "1") (pinfunction "1_1") (pintype "passive"))
      (node (ref "FR45") (pin "1") (pinfunction "1_1") (pintype "passive"))
      (node (ref "FR46") (pin "1") (pinfunction "1_1") (pintype "passive"))
      (node (ref "IC19") (pin "16") (pinfunction "DVdd_16") (pintype "passive"))
      (node (ref "IC19") (pin "17") (pinfunction "DVdd_17") (pintype "passive"))
      (node (ref "IC20") (pin "14") (pinfunction "VDDOD_14") (pintype "passive"))
      (node (ref "IC20") (pin "18") (pinfunction "VDDOC_18") (pintype "passive"))
      (node (ref "IC20") (pin "20") (pinfunction "VDD_20") (pintype "passive"))
      (node (ref "R112") (pin "1") (pinfunction "1_1") (pintype "passive"))
      (node (ref "R123") (pin "2") (pinfunction "2_2") (pintype "passive"))
      (node (ref "R124") (pin "2") (pinfunction "2_2") (pintype "passive"))
    )
    (net (code "62") (name "VCC3P3_LMK") (class "Default")
      (node (ref "C320") (pin "2") (pinfunction "2_2") (pintype "passive"))
      (node (ref "C321") (pin "2") (pinfunction "2_2") (pintype "passive"))
      (node (ref "C322") (pin "2") (pinfunction "2_2") (pintype "passive"))
      (node (ref "C323") (pin "2") (pinfunction "2_2") (pintype "passive"))
      (node (ref "FR41") (pin "2") (pinfunction "2_2") (pintype "passive"))
      (node (ref "IC16") (pin "23") (pinfunction "Vdd_23") (pintype "passive"))
      (node (ref "IC16") (pin "8") (pinfunction "Vdd_8") (pintype "passive"))
      (node (ref "R106") (pin "2") (pinfunction "2_2") (pintype "passive"))
      (node (ref "R119") (pin "1") (pinfunction "1_1") (pintype "passive"))
    )
    (net (code "63") (name "VDIO_LMK") (class "Default")
      (node (ref "C328") (pin "2") (pinfunction "2_2") (pintype "passive"))
      (node (ref "C329") (pin "2") (pinfunction "2_2") (pintype "passive"))
      (node (ref "C330") (pin "2") (pinfunction "2_2") (pintype "passive"))
      (node (ref "C331") (pin "2") (pinfunction "2_2") (pintype "passive"))
      (node (ref "FR43") (pin "2") (pinfunction "2_2") (pintype "passive"))
      (node (ref "IC16") (pin "14") (pinfunction "Vddo_14") (pintype "passive"))
      (node (ref "IC16") (pin "18") (pinfunction "Vddo_18") (pintype "passive"))
    )
    (net (code "64") (name "VDIO_LMS_FPGA") (class "Default")
      (node (ref "C350") (pin "1") (pinfunction "1_1") (pintype "passive"))
      (node (ref "C351") (pin "1") (pinfunction "1_1") (pintype "passive"))
      (node (ref "IC20") (pin "10") (pinfunction "VDDOB_10") (pintype "passive"))
      (node (ref "IC20") (pin "11") (pinfunction "VDDOA_11") (pintype "passive"))
      (node (ref "R119") (pin "2") (pinfunction "2_2") (pintype "passive"))
    )
    (net (code "65") (name "unconnected-(IC16-OSCin-Pad9)") (class "Default")
      (node (ref "IC16") (pin "9") (pinfunction "OSCin_9") (pintype "passive+no_connect"))
    )
    (net (code "66") (name "unconnected-(IC16-OSCout-Pad10)") (class "Default")
      (node (ref "IC16") (pin "10") (pinfunction "OSCout_10") (pintype "passive+no_connect"))
    )
    (net (code "67") (name "unconnected-(IC20-CLK5-Pad17)") (class "Default")
      (node (ref "IC20") (pin "17") (pinfunction "CLK5_17") (pintype "passive+no_connect"))
    )
    (net (code "68") (name "unconnected-(IC20-CLK7-Pad15)") (class "Default")
      (node (ref "IC20") (pin "15") (pinfunction "CLK7_15") (pintype "passive+no_connect"))
    )
    (net (code "69") (name "unconnected-(IC20-INTR-Pad3)") (class "Default")
      (node (ref "IC20") (pin "3") (pinfunction "INTR_3") (pintype "passive+no_connect"))
    )
    (net (code "70") (name "unconnected-(XO1-T.S.-Pad3)") (class "Default")
      (node (ref "XO1") (pin "3") (pinfunction "T.S._3") (pintype "passive+no_connect"))
    )
  )
)
